# Fixture_07.net
KiCad netlist of a schematic drawn in Altium Designer
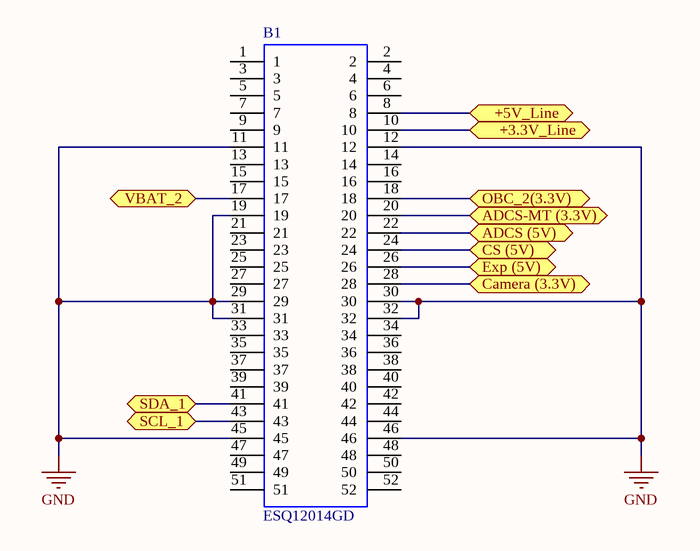
[diagram p0: Fixture_07.SchDoc]

(export (version "E")
  (design (tool "Eeschema 10.0.6"))
  (components
    (comp (ref "B1")
      (value "ESQ12014GD")
      (footprint "PinHeader104")
      (fields (field (name "RS PART NUMBER") "2546110"))
      (libsource (lib "Schlib1") (part "ESQ12014GD"))
    )
  )
  (nets
    (net (code "1") (name "/+3.3V_Line") (class "Default")
      (node (ref "B1") (pin "10") (pinfunction "10_10") (pintype "passive"))
    )
    (net (code "2") (name "/+5V_Line") (class "Default")
      (node (ref "B1") (pin "8") (pinfunction "8_8") (pintype "passive"))
    )
    (net (code "3") (name "/ADCS (5V)") (class "Default")
      (node (ref "B1") (pin "22") (pinfunction "22_22") (pintype "passive"))
    )
    (net (code "4") (name "/ADCS-MT (3.3V)") (class "Default")
      (node (ref "B1") (pin "20") (pinfunction "20_20") (pintype "passive"))
    )
    (net (code "5") (name "/CS (5V)") (class "Default")
      (node (ref "B1") (pin "24") (pinfunction "24_24") (pintype "passive"))
    )
    (net (code "6") (name "/Camera (3.3V)") (class "Default")
      (node (ref "B1") (pin "28") (pinfunction "28_28") (pintype "passive"))
    )
    (net (code "7") (name "/Exp (5V)") (class "Default")
      (node (ref "B1") (pin "26") (pinfunction "26_26") (pintype "passive"))
    )
    (net (code "8") (name "/OBC_2(3.3V)") (class "Default")
      (node (ref "B1") (pin "18") (pinfunction "18_18") (pintype "passive"))
    )
    (net (code "9") (name "/SCL_1") (class "Default")
      (node (ref "B1") (pin "43") (pinfunction "43_43") (pintype "passive"))
    )
    (net (code "10") (name "/SDA_1") (class "Default")
      (node (ref "B1") (pin "41") (pinfunction "41_41") (pintype "passive"))
    )
    (net (code "11") (name "/VBAT_2") (class "Default")
      (node (ref "B1") (pin "17") (pinfunction "17_17") (pintype "passive"))
    )
    (net (code "12") (name "GND") (class "Default")
      (node (ref "B1") (pin "11") (pinfunction "11_11") (pintype "passive"))
      (node (ref "B1") (pin "12") (pinfunction "12_12") (pintype "passive"))
      (node (ref "B1") (pin "19") (pinfunction "19_19") (pintype "passive"))
      (node (ref "B1") (pin "29") (pinfunction "29_29") (pintype "passive"))
      (node (ref "B1") (pin "30") (pinfunction "30_30") (pintype "passive"))
      (node (ref "B1") (pin "31") (pinfunction "31_31") (pintype "passive"))
      (node (ref "B1") (pin "32") (pinfunction "32_32") (pintype "passive"))
      (node (ref "B1") (pin "45") (pinfunction "45_45") (pintype "passive"))
      (node (ref "B1") (pin "46") (pinfunction "46_46") (pintype "passive"))
    )
    (net (code "13") (name "unconnected-(B1-Pad1)") (class "Default")
      (node (ref "B1") (pin "1") (pinfunction "1_1") (pintype "passive"))
    )
    (net (code "14") (name "unconnected-(B1-Pad2)") (class "Default")
      (node (ref "B1") (pin "2") (pinfunction "2_2") (pintype "passive"))
    )
    (net (code "15") (name "unconnected-(B1-Pad3)") (class "Default")
      (node (ref "B1") (pin "3") (pinfunction "3_3") (pintype "passive"))
    )
    (net (code "16") (name "unconnected-(B1-Pad4)") (class "Default")
      (node (ref "B1") (pin "4") (pinfunction "4_4") (pintype "passive"))
    )
    (net (code "17") (name "unconnected-(B1-Pad5)") (class "Default")
      (node (ref "B1") (pin "5") (pinfunction "5_5") (pintype "passive"))
    )
    (net (code "18") (name "unconnected-(B1-Pad6)") (class "Default")
      (node (ref "B1") (pin "6") (pinfunction "6_6") (pintype "passive"))
    )
    (net (code "19") (name "unconnected-(B1-Pad7)") (class "Default")
      (node (ref "B1") (pin "7") (pinfunction "7_7") (pintype "passive"))
    )
    (net (code "20") (name "unconnected-(B1-Pad9)") (class "Default")
      (node (ref "B1") (pin "9") (pinfunction "9_9") (pintype "passive"))
    )
    (net (code "21") (name "unconnected-(B1-Pad13)") (class "Default")
      (node (ref "B1") (pin "13") (pinfunction "13_13") (pintype "passive"))
    )
    (net (code "22") (name "unconnected-(B1-Pad14)") (class "Default")
      (node (ref "B1") (pin "14") (pinfunction "14_14") (pintype "passive"))
    )
    (net (code "23") (name "unconnected-(B1-Pad15)") (class "Default")
      (node (ref "B1") (pin "15") (pinfunction "15_15") (pintype "passive"))
    )
    (net (code "24") (name "unconnected-(B1-Pad16)") (class "Default")
      (node (ref "B1") (pin "16") (pinfunction "16_16") (pintype "passive"))
    )
    (net (code "25") (name "unconnected-(B1-Pad21)") (class "Default")
      (node (ref "B1") (pin "21") (pinfunction "21_21") (pintype "passive"))
    )
    (net (code "26") (name "unconnected-(B1-Pad23)") (class "Default")
      (node (ref "B1") (pin "23") (pinfunction "23_23") (pintype "passive"))
    )
    (net (code "27") (name "unconnected-(B1-Pad25)") (class "Default")
      (node (ref "B1") (pin "25") (pinfunction "25_25") (pintype "passive"))
    )
    (net (code "28") (name "unconnected-(B1-Pad27)") (class "Default")
      (node (ref "B1") (pin "27") (pinfunction "27_27") (pintype "passive"))
    )
    (net (code "29") (name "unconnected-(B1-Pad33)") (class "Default")
      (node (ref "B1") (pin "33") (pinfunction "33_33") (pintype "passive"))
    )
    (net (code "30") (name "unconnected-(B1-Pad34)") (class "Default")
      (node (ref "B1") (pin "34") (pinfunction "34_34") (pintype "passive"))
    )
    (net (code "31") (name "unconnected-(B1-Pad35)") (class "Default")
      (node (ref "B1") (pin "35") (pinfunction "35_35") (pintype "passive"))
    )
    (net (code "32") (name "unconnected-(B1-Pad36)") (class "Default")
      (node (ref "B1") (pin "36") (pinfunction "36_36") (pintype "passive"))
    )
    (net (code "33") (name "unconnected-(B1-Pad37)") (class "Default")
      (node (ref "B1") (pin "37") (pinfunction "37_37") (pintype "passive"))
    )
    (net (code "34") (name "unconnected-(B1-Pad38)") (class "Default")
      (node (ref "B1") (pin "38") (pinfunction "38_38") (pintype "passive"))
    )
    (net (code "35") (name "unconnected-(B1-Pad39)") (class "Default")
      (node (ref "B1") (pin "39") (pinfunction "39_39") (pintype "passive"))
    )
    (net (code "36") (name "unconnected-(B1-Pad40)") (class "Default")
      (node (ref "B1") (pin "40") (pinfunction "40_40") (pintype "passive"))
    )
    (net (code "37") (name "unconnected-(B1-Pad42)") (class "Default")
      (node (ref "B1") (pin "42") (pinfunction "42_42") (pintype "passive"))
    )
    (net (code "38") (name "unconnected-(B1-Pad44)") (class "Default")
      (node (ref "B1") (pin "44") (pinfunction "44_44") (pintype "passive"))
    )
    (net (code "39") (name "unconnected-(B1-Pad47)") (class "Default")
      (node (ref "B1") (pin "47") (pinfunction "47_47") (pintype "passive"))
    )
    (net (code "40") (name "unconnected-(B1-Pad48)") (class "Default")
      (node (ref "B1") (pin "48") (pinfunction "48_48") (pintype "passive"))
    )
    (net (code "41") (name "unconnected-(B1-Pad49)") (class "Default")
      (node (ref "B1") (pin "49") (pinfunction "49_49") (pintype "passive"))
    )
    (net (code "42") (name "unconnected-(B1-Pad50)") (class "Default")
      (node (ref "B1") (pin "50") (pinfunction "50_50") (pintype "passive"))
    )
    (net (code "43") (name "unconnected-(B1-Pad51)") (class "Default")
      (node (ref "B1") (pin "51") (pinfunction "51_51") (pintype "passive"))
    )
    (net (code "44") (name "unconnected-(B1-Pad52)") (class "Default")
      (node (ref "B1") (pin "52") (pinfunction "52_52") (pintype "passive"))
    )
  )
)
